# dmx.net
KiCad netlist of a schematic drawn in EAGLE
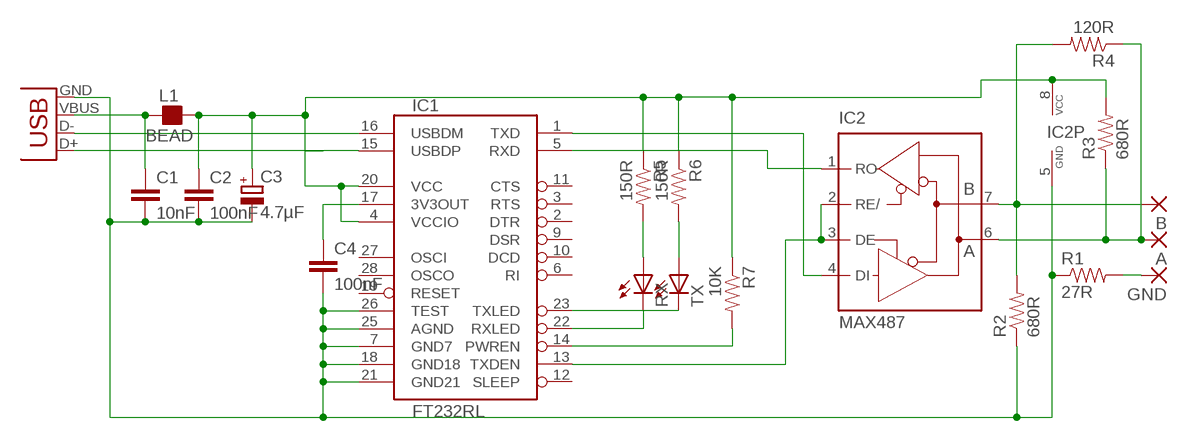
[diagram p0: schematic, sheet 1]

(export (version "E")
  (design (tool "Eeschema 10.0.6"))
  (components
    (comp (ref "A")
      (value "SMD5")
      (footprint "eagle-import:SMD2,54-5,08")
      (libsource (lib "eagle-import") (part "SMD5"))
    )
    (comp (ref "B")
      (value "SMD5")
      (footprint "eagle-import:SMD2,54-5,08")
      (libsource (lib "eagle-import") (part "SMD5"))
    )
    (comp (ref "C1")
      (value "10nF")
      (footprint "eagle-import:0805")
      (libsource (lib "eagle-import") (part "CAP0805"))
    )
    (comp (ref "C2")
      (value "100nF")
      (footprint "eagle-import:0805")
      (libsource (lib "eagle-import") (part "CAP0805"))
    )
    (comp (ref "C3")
      (value "4.7µF")
      (footprint "eagle-import:SMC_C")
      (libsource (lib "eagle-import") (part "CPOL-EUSMCC"))
    )
    (comp (ref "C4")
      (value "100nF")
      (footprint "eagle-import:0805")
      (libsource (lib "eagle-import") (part "CAP0805"))
    )
    (comp (ref "GND")
      (value "SMD5")
      (footprint "eagle-import:SMD2,54-5,08")
      (libsource (lib "eagle-import") (part "SMD5"))
    )
    (comp (ref "IC1")
      (value "FT232RL")
      (footprint "eagle-import:SSOP28DB")
      (libsource (lib "eagle-import") (part "FT232RLSSOP"))
    )
    (comp (ref "IC2")
      (value "MAX487")
      (footprint "eagle-import:SO08")
      (fields (field (name "MF") "MAXIM") (field (name "MPN") "MAX481CSA"))
      (libsource (lib "eagle-import") (part "MAX481CSA"))
    )
    (comp (ref "L1")
      (value "BEAD")
      (footprint "eagle-import:L0805")
      (libsource (lib "eagle-import") (part "FB_0805"))
    )
    (comp (ref "R1")
      (value "27R")
      (footprint "eagle-import:0805")
      (libsource (lib "eagle-import") (part "RESISTOR0805-RES"))
    )
    (comp (ref "R2")
      (value "680R")
      (footprint "eagle-import:0805")
      (libsource (lib "eagle-import") (part "RESISTOR0805-RES"))
    )
    (comp (ref "R3")
      (value "680R")
      (footprint "eagle-import:0805")
      (libsource (lib "eagle-import") (part "RESISTOR0805-RES"))
    )
    (comp (ref "R4")
      (value "120R")
      (footprint "eagle-import:0805")
      (libsource (lib "eagle-import") (part "RESISTOR0805-RES"))
    )
    (comp (ref "R5")
      (value "150R")
      (footprint "eagle-import:0805")
      (libsource (lib "eagle-import") (part "RESISTOR0805-RES"))
    )
    (comp (ref "R6")
      (value "150R")
      (footprint "eagle-import:0805")
      (libsource (lib "eagle-import") (part "RESISTOR0805-RES"))
    )
    (comp (ref "R7")
      (value "10K")
      (footprint "eagle-import:0805")
      (libsource (lib "eagle-import") (part "RESISTOR0805-RES"))
    )
    (comp (ref "RX")
      (value "LEDCHIP-LED0805")
      (footprint "eagle-import:CHIP-LED0805")
      (libsource (lib "eagle-import") (part "LEDCHIP-LED0805"))
    )
    (comp (ref "TX")
      (value "LEDCHIP-LED0805")
      (footprint "eagle-import:CHIP-LED0805")
      (libsource (lib "eagle-import") (part "LEDCHIP-LED0805"))
    )
    (comp (ref "X7")
      (value "USB-SMD-NS")
      (footprint "eagle-import:USB-MINIB-NOSTOP")
      (libsource (lib "eagle-import") (part "USB-SMD-NS"))
    )
  )
  (nets
    (net (code "1") (name "Net-(A-P)") (class "Default")
      (node (ref "A") (pin "1") (pinfunction "P_1") (pintype "passive"))
      (node (ref "IC2") (pin "6") (pinfunction "A_6") (pintype "passive"))
      (node (ref "R3") (pin "1") (pinfunction "1_1") (pintype "passive"))
      (node (ref "R4") (pin "1") (pinfunction "1_1") (pintype "passive"))
    )
    (net (code "2") (name "Net-(B-P)") (class "Default")
      (node (ref "B") (pin "1") (pinfunction "P_1") (pintype "passive"))
      (node (ref "IC2") (pin "7") (pinfunction "B_7") (pintype "passive"))
      (node (ref "R2") (pin "2") (pinfunction "2_2") (pintype "passive"))
      (node (ref "R4") (pin "2") (pinfunction "2_2") (pintype "passive"))
    )
    (net (code "3") (name "Net-(C1-Pad1)") (class "Default")
      (node (ref "C1") (pin "1") (pinfunction "1_1") (pintype "passive"))
      (node (ref "L1") (pin "1") (pinfunction "1_1") (pintype "passive"))
      (node (ref "X7") (pin "VBUS") (pinfunction "VBUS_VBUS") (pintype "bidirectional"))
    )
    (net (code "4") (name "Net-(GND-P)") (class "Default")
      (node (ref "GND") (pin "1") (pinfunction "P_1") (pintype "passive"))
      (node (ref "R1") (pin "2") (pinfunction "2_2") (pintype "passive"))
    )
    (net (code "5") (name "Net-(IC1-3V3OUT)") (class "Default")
      (node (ref "C4") (pin "1") (pinfunction "1_1") (pintype "passive"))
      (node (ref "IC1") (pin "17") (pinfunction "3V3OUT_17") (pintype "output"))
    )
    (net (code "6") (name "Net-(IC1-AGND)") (class "Default")
      (node (ref "C1") (pin "2") (pinfunction "2_2") (pintype "passive"))
      (node (ref "C2") (pin "2") (pinfunction "2_2") (pintype "passive"))
      (node (ref "C3") (pin "-") (pinfunction "-_-") (pintype "passive"))
      (node (ref "C4") (pin "2") (pinfunction "2_2") (pintype "passive"))
      (node (ref "IC1") (pin "18") (pinfunction "GND18_18") (pintype "power_in"))
      (node (ref "IC1") (pin "21") (pinfunction "GND21_21") (pintype "power_in"))
      (node (ref "IC1") (pin "25") (pinfunction "AGND_25") (pintype "power_in"))
      (node (ref "IC1") (pin "26") (pinfunction "TEST_26") (pintype "input"))
      (node (ref "IC1") (pin "7") (pinfunction "GND7_7") (pintype "power_in"))
      (node (ref "IC2") (pin "5") (pinfunction "GND_5") (pintype "power_in"))
      (node (ref "R1") (pin "1") (pinfunction "1_1") (pintype "passive"))
      (node (ref "R2") (pin "1") (pinfunction "1_1") (pintype "passive"))
      (node (ref "X7") (pin "GND") (pinfunction "GND_GND") (pintype "bidirectional"))
    )
    (net (code "7") (name "Net-(IC1-PWREN)") (class "Default")
      (node (ref "IC1") (pin "14") (pinfunction "PWREN_14") (pintype "input"))
      (node (ref "R7") (pin "2") (pinfunction "2_2") (pintype "passive"))
    )
    (net (code "8") (name "Net-(IC1-RXD)") (class "Default")
      (node (ref "IC1") (pin "5") (pinfunction "RXD_5") (pintype "input"))
      (node (ref "IC2") (pin "1") (pinfunction "RO_1") (pintype "output"))
    )
    (net (code "9") (name "Net-(IC1-RXLED)") (class "Default")
      (node (ref "IC1") (pin "22") (pinfunction "RXLED_22") (pintype "input"))
      (node (ref "RX") (pin "C") (pinfunction "C_C") (pintype "passive"))
    )
    (net (code "10") (name "Net-(IC1-TXD)") (class "Default")
      (node (ref "IC1") (pin "1") (pinfunction "TXD_1") (pintype "output"))
      (node (ref "IC2") (pin "4") (pinfunction "DI_4") (pintype "input"))
    )
    (net (code "11") (name "Net-(IC1-TXDEN)") (class "Default")
      (node (ref "IC1") (pin "13") (pinfunction "TXDEN_13") (pintype "input"))
      (node (ref "IC2") (pin "2") (pinfunction "RE/_2") (pintype "input"))
      (node (ref "IC2") (pin "3") (pinfunction "DE_3") (pintype "input"))
    )
    (net (code "12") (name "Net-(IC1-TXLED)") (class "Default")
      (node (ref "IC1") (pin "23") (pinfunction "TXLED_23") (pintype "input"))
      (node (ref "TX") (pin "C") (pinfunction "C_C") (pintype "passive"))
    )
    (net (code "13") (name "Net-(IC1-USBDM)") (class "Default")
      (node (ref "IC1") (pin "16") (pinfunction "USBDM_16") (pintype "bidirectional"))
      (node (ref "X7") (pin "D-") (pinfunction "D-_D-") (pintype "bidirectional"))
    )
    (net (code "14") (name "Net-(IC1-USBDP)") (class "Default")
      (node (ref "IC1") (pin "15") (pinfunction "USBDP_15") (pintype "bidirectional"))
      (node (ref "X7") (pin "D+") (pinfunction "D+_D+") (pintype "bidirectional"))
    )
    (net (code "15") (name "Net-(IC1-VCC)") (class "Default")
      (node (ref "C2") (pin "1") (pinfunction "1_1") (pintype "passive"))
      (node (ref "C3") (pin "+") (pinfunction "+_+") (pintype "passive"))
      (node (ref "IC1") (pin "20") (pinfunction "VCC_20") (pintype "power_in"))
      (node (ref "IC1") (pin "4") (pinfunction "VCCIO_4") (pintype "power_in"))
      (node (ref "IC2") (pin "8") (pinfunction "VCC_8") (pintype "power_in"))
      (node (ref "L1") (pin "2") (pinfunction "2_2") (pintype "passive"))
      (node (ref "R3") (pin "2") (pinfunction "2_2") (pintype "passive"))
      (node (ref "R5") (pin "1") (pinfunction "1_1") (pintype "passive"))
      (node (ref "R6") (pin "1") (pinfunction "1_1") (pintype "passive"))
      (node (ref "R7") (pin "1") (pinfunction "1_1") (pintype "passive"))
    )
    (net (code "16") (name "Net-(R5-Pad2)") (class "Default")
      (node (ref "R5") (pin "2") (pinfunction "2_2") (pintype "passive"))
      (node (ref "RX") (pin "A") (pinfunction "A_A") (pintype "passive"))
    )
    (net (code "17") (name "Net-(R6-Pad2)") (class "Default")
      (node (ref "R6") (pin "2") (pinfunction "2_2") (pintype "passive"))
      (node (ref "TX") (pin "A") (pinfunction "A_A") (pintype "passive"))
    )
    (net (code "18") (name "unconnected-(IC1-CTS-Pad11)") (class "Default")
      (node (ref "IC1") (pin "11") (pinfunction "CTS_11") (pintype "input"))
    )
    (net (code "19") (name "unconnected-(IC1-DCD-Pad10)") (class "Default")
      (node (ref "IC1") (pin "10") (pinfunction "DCD_10") (pintype "input"))
    )
    (net (code "20") (name "unconnected-(IC1-DSR-Pad9)") (class "Default")
      (node (ref "IC1") (pin "9") (pinfunction "DSR_9") (pintype "input"))
    )
    (net (code "21") (name "unconnected-(IC1-DTR-Pad2)") (class "Default")
      (node (ref "IC1") (pin "2") (pinfunction "DTR_2") (pintype "output"))
    )
    (net (code "22") (name "unconnected-(IC1-OSCI-Pad27)") (class "Default")
      (node (ref "IC1") (pin "27") (pinfunction "OSCI_27") (pintype "input"))
    )
    (net (code "23") (name "unconnected-(IC1-OSCO-Pad28)") (class "Default")
      (node (ref "IC1") (pin "28") (pinfunction "OSCO_28") (pintype "output"))
    )
    (net (code "24") (name "unconnected-(IC1-RESET-Pad19)") (class "Default")
      (node (ref "IC1") (pin "19") (pinfunction "RESET_19") (pintype "input"))
    )
    (net (code "25") (name "unconnected-(IC1-RI-Pad6)") (class "Default")
      (node (ref "IC1") (pin "6") (pinfunction "RI_6") (pintype "input"))
    )
    (net (code "26") (name "unconnected-(IC1-RTS-Pad3)") (class "Default")
      (node (ref "IC1") (pin "3") (pinfunction "RTS_3") (pintype "output"))
    )
    (net (code "27") (name "unconnected-(IC1-SLEEP-Pad12)") (class "Default")
      (node (ref "IC1") (pin "12") (pinfunction "SLEEP_12") (pintype "input"))
    )
  )
)
